# STM32f103c8t6.net
KiCad netlist of a schematic drawn in Altium Designer
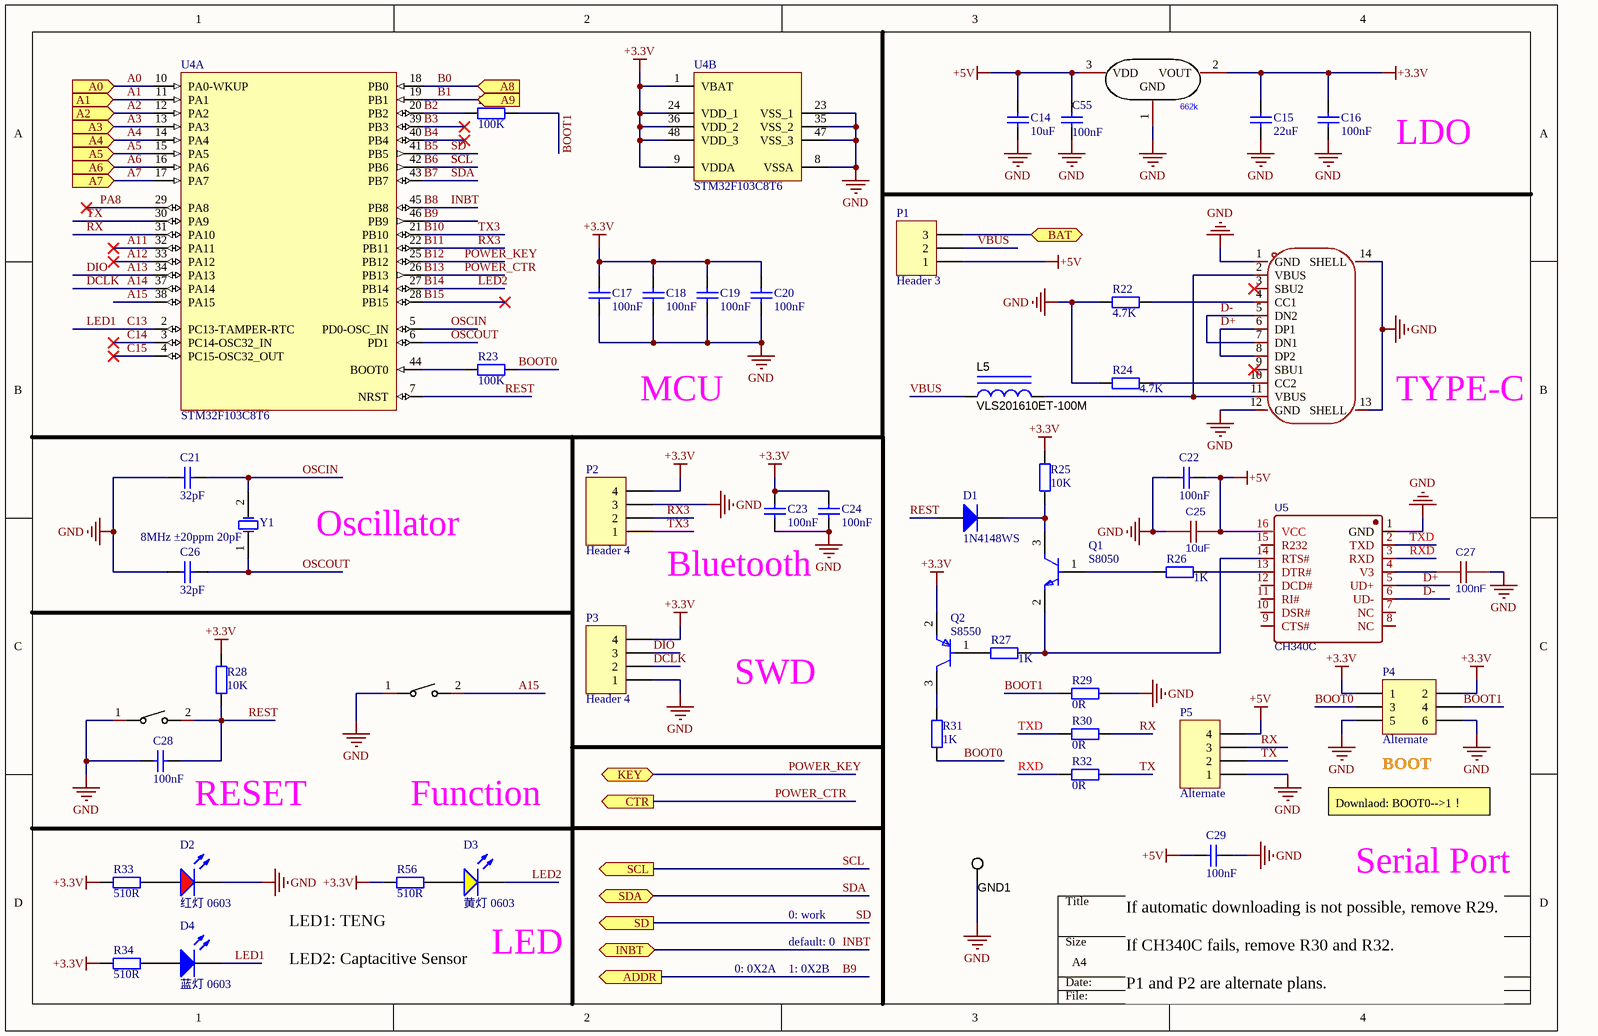
[diagram p0: STM32f103c8t6.SchDoc]

(export (version "E")
  (design (tool "Eeschema 10.0.6"))
  (components
    (comp (ref "C14")
      (value "10uF")
      (footprint "FDC2214:0603")
      (description "0402贴片电容")
      (libsource (lib "02-Miscellaneous_Devices_ZSF_Library") (part "Cap_0402"))
    )
    (comp (ref "C15")
      (value "22uF")
      (footprint "FDC2214:0603")
      (description "0402贴片电容")
      (libsource (lib "02-Miscellaneous_Devices_ZSF_Library") (part "Cap_0402"))
    )
    (comp (ref "C16")
      (value "100nF")
      (footprint "0402_C")
      (description "0402贴片电容")
      (libsource (lib "02-Miscellaneous_Devices_ZSF_Library") (part "Cap_0402"))
    )
    (comp (ref "C17")
      (value "100nF")
      (footprint "0402_C")
      (description "0402贴片电容")
      (libsource (lib "02-Miscellaneous_Devices_ZSF_Library") (part "Cap_0402"))
    )
    (comp (ref "C18")
      (value "100nF")
      (footprint "0402_C")
      (description "0402贴片电容")
      (libsource (lib "02-Miscellaneous_Devices_ZSF_Library") (part "Cap_0402"))
    )
    (comp (ref "C19")
      (value "100nF")
      (footprint "0402_C")
      (description "0402贴片电容")
      (libsource (lib "02-Miscellaneous_Devices_ZSF_Library") (part "Cap_0402"))
    )
    (comp (ref "C20")
      (value "100nF")
      (footprint "0402_C")
      (description "0402贴片电容")
      (libsource (lib "02-Miscellaneous_Devices_ZSF_Library") (part "Cap_0402"))
    )
    (comp (ref "C21")
      (value "32pF")
      (footprint "0402_C")
      (description "0402贴片电容")
      (libsource (lib "02-Miscellaneous_Devices_ZSF_Library") (part "Cap_0402"))
    )
    (comp (ref "C22")
      (value "100nF")
      (footprint "0402_C")
      (description "0402贴片电容")
      (libsource (lib "02-Miscellaneous_Devices_ZSF_Library") (part "Cap_0402"))
    )
    (comp (ref "C23")
      (value "100nF")
      (footprint "0402_C")
      (description "0402贴片电容")
      (libsource (lib "02-Miscellaneous_Devices_ZSF_Library") (part "Cap_0402"))
    )
    (comp (ref "C24")
      (value "100nF")
      (footprint "0402_C")
      (description "0402贴片电容")
      (libsource (lib "02-Miscellaneous_Devices_ZSF_Library") (part "Cap_0402"))
    )
    (comp (ref "C25")
      (value "10uF")
      (footprint "0402_C")
      (fields
        (field (name "BOM_MANUFACTURER PART") "XH414HG-IV01E")
        (field (name "BOM_SUPPLIER PART") "C38065")
      )
      (libsource (lib "XR_ADSCH_Library") (part "C"))
    )
    (comp (ref "C26")
      (value "32pF")
      (footprint "0402_C")
      (description "0402贴片电容")
      (libsource (lib "02-Miscellaneous_Devices_ZSF_Library") (part "Cap_0402"))
    )
    (comp (ref "C27")
      (value "100nF")
      (footprint "0402_C")
      (fields
        (field (name "BOM_MANUFACTURER PART") "XH414HG-IV01E")
        (field (name "BOM_SUPPLIER PART") "C38065")
      )
      (libsource (lib "XR_ADSCH_Library") (part "C"))
    )
    (comp (ref "C28")
      (value "100nF")
      (footprint "0402_C")
      (description "0402贴片电容")
      (libsource (lib "02-Miscellaneous_Devices_ZSF_Library") (part "Cap_0402"))
    )
    (comp (ref "C29")
      (value "100nF")
      (footprint "0402_C")
      (description "0402贴片电容")
      (libsource (lib "02-Miscellaneous_Devices_ZSF_Library") (part "Cap_0402"))
    )
    (comp (ref "C55")
      (value "100nF")
      (footprint "0402_C")
      (description "0402贴片电容")
      (libsource (lib "02-Miscellaneous_Devices_ZSF_Library") (part "Cap_0402"))
    )
    (comp (ref "D1")
      (value "1N4148WS")
      (footprint "SOD-323")
      (description "二极管")
      (libsource (lib "02-Miscellaneous_Devices_ZSF_Library") (part "1N4148WS_SOD-323"))
    )
    (comp (ref "D2")
      (value "红灯 0603")
      (footprint "0603_LED_S1")
      (description "发光二极管")
      (libsource (lib "02-Miscellaneous_Devices_ZSF_Library") (part "0603 红灯"))
    )
    (comp (ref "D3")
      (value "黄灯 0603")
      (footprint "0603_LED_S1")
      (description "发光二极管")
      (libsource (lib "02-Miscellaneous_Devices_ZSF_Library") (part "0603 黄灯"))
    )
    (comp (ref "D4")
      (value "蓝灯 0603")
      (footprint "0603_LED_S1")
      (description "发光二极管")
      (libsource (lib "02-Miscellaneous_Devices_ZSF_Library") (part "0603 蓝灯"))
    )
    (comp (ref "GND1")
      (value "5015")
      (footprint "Testpoint_Keystone_Miniature")
      (description "Test Point, Miniature, SMT")
      (fields (field (name "MANUFACTURER") "Keystone") (field (name "PUBLISHER") "Texas Instruments"))
      (libsource (lib "Connectors_Keystone") (part "5015"))
    )
    (comp (ref "L5")
      (value "VLS201610ET-100M")
      (footprint "VLS201610ET")
      (description "Inductor, Shielded, Ferrite, 10 μH, 0.4 A, 1.38 ohm, SMD")
      (fields (field (name "MANUFACTURER") "TDK") (field (name "PUBLISHER") "Texas Instruments"))
      (libsource (lib "Inductor_TDK") (part "VLS201610ET-100M"))
    )
    (comp (ref "LDO1")
      (value "662k")
      (footprint "SOT-23-3_L2.9-W1.3-P1.90-LS2.4-BR")
      (fields (field (name "MANUFACTURER") "FM(富满)") (field (name "MANUFACTURER PART") "SC662K-3.3V"))
      (libsource (lib "Chip") (part "SC662K-3.3V"))
    )
    (comp (ref "P1")
      (value "Header 3")
      (footprint "SIP-3")
      (description "Header, 3-Pin")
      (fields (field (name "PUBLISHER") "Altium Limited"))
      (libsource (lib "01-Connect_IntegratedLibrary") (part "Header 3"))
    )
    (comp (ref "P2")
      (value "Header 4")
      (footprint "XH254-4")
      (description "Header, 4-Pin")
      (fields (field (name "PUBLISHER") "Altium Limited"))
      (libsource (lib "01-Connect_IntegratedLibrary") (part "Header 4"))
    )
    (comp (ref "P3")
      (value "Header 4")
      (footprint "SIP-4")
      (description "Header, 4-Pin")
      (fields (field (name "PUBLISHER") "Altium Limited"))
      (libsource (lib "01-Connect_IntegratedLibrary") (part "Header 4"))
    )
    (comp (ref "P4")
      (value "Alternate")
      (footprint "01-Connect_IntegratedLibrary:HDR2X3 - SMT")
      (description "Header, 3-Pin, Dual row")
      (fields (field (name "PUBLISHER") "Altium Limited"))
      (libsource (lib "01-Connect_IntegratedLibrary") (part "Header 3X2"))
    )
    (comp (ref "P5")
      (value "Alternate")
      (footprint "SIP-4")
      (description "Header, 4-Pin")
      (fields (field (name "PUBLISHER") "Altium Limited"))
      (libsource (lib "01-Connect_IntegratedLibrary") (part "Header 4"))
    )
    (comp (ref "Q1")
      (value "S8050")
      (footprint "FP-SS8050-G-IPC_B")
      (description "NPN TRANSISTOR 1.5A 40V SOT-23 R")
      (libsource (lib "Chip") (part "S8050"))
    )
    (comp (ref "Q2")
      (value "S8550")
      (footprint "FP-SOT-23-IPC_A")
      (description "TRANS PNP 25V 1.5A SOT23")
      (libsource (lib "Chip") (part "S8550"))
    )
    (comp (ref "R21")
      (value "100K")
      (footprint "0402_R")
      (description "贴片电阻")
      (libsource (lib "02-Miscellaneous_Devices_ZSF_Library") (part "Res_0402"))
    )
    (comp (ref "R22")
      (value "4.7K")
      (footprint "0402_R")
      (description "贴片电阻")
      (libsource (lib "02-Miscellaneous_Devices_ZSF_Library") (part "Res_0402"))
    )
    (comp (ref "R23")
      (value "100K")
      (footprint "0402_R")
      (description "贴片电阻")
      (libsource (lib "02-Miscellaneous_Devices_ZSF_Library") (part "Res_0402"))
    )
    (comp (ref "R24")
      (value "4.7K")
      (footprint "0402_R")
      (description "贴片电阻")
      (libsource (lib "02-Miscellaneous_Devices_ZSF_Library") (part "Res_0402"))
    )
    (comp (ref "R25")
      (value "10K")
      (footprint "0402_R")
      (description "贴片电阻")
      (libsource (lib "") (part "Res_0402_1"))
    )
    (comp (ref "R26")
      (value "1K")
      (footprint "0402_R")
      (description "贴片电阻")
      (libsource (lib "02-Miscellaneous_Devices_ZSF_Library") (part "Res_0402"))
    )
    (comp (ref "R27")
      (value "1K")
      (footprint "0402_R")
      (description "贴片电阻")
      (libsource (lib "02-Miscellaneous_Devices_ZSF_Library") (part "Res_0402"))
    )
    (comp (ref "R28")
      (value "10K")
      (footprint "0402_R")
      (description "贴片电阻")
      (libsource (lib "") (part "Res_0402_1"))
    )
    (comp (ref "R29")
      (value "0R")
      (footprint "0805_R")
      (description "0805贴片电阻")
      (libsource (lib "02-Miscellaneous_Devices_ZSF_Library") (part "Res_0805"))
    )
    (comp (ref "R30")
      (value "0R")
      (footprint "0805_R")
      (description "0805贴片电阻")
      (libsource (lib "02-Miscellaneous_Devices_ZSF_Library") (part "Res_0805"))
    )
    (comp (ref "R31")
      (value "1K")
      (footprint "0402_R")
      (description "0805贴片电阻")
      (libsource (lib "") (part "Res_0805_1"))
    )
    (comp (ref "R32")
      (value "0R")
      (footprint "0805_R")
      (description "0805贴片电阻")
      (libsource (lib "02-Miscellaneous_Devices_ZSF_Library") (part "Res_0805"))
    )
    (comp (ref "R33")
      (value "510R")
      (footprint "0402_R")
      (description "贴片电阻")
      (libsource (lib "") (part "Res_0402_2"))
    )
    (comp (ref "R34")
      (value "510R")
      (footprint "0402_R")
      (description "贴片电阻")
      (libsource (lib "") (part "Res_0402_2"))
    )
    (comp (ref "R56")
      (value "510R")
      (footprint "0402_R")
      (description "贴片电阻")
      (libsource (lib "") (part "Res_0402_2"))
    )
    (comp (ref "SW1")
      (value "TS-1088-AR02016")
      (footprint "SW-SMD_L3.9-W3.0-P4.45")
      (fields (field (name "MANUFACTURER") "XUNPU(讯普)"))
      (libsource (lib "Chip") (part "Key"))
    )
    (comp (ref "SW2")
      (value "TS-1088-AR02016")
      (footprint "SW-SMD_L3.9-W3.0-P4.45")
      (fields (field (name "MANUFACTURER") "XUNPU(讯普)"))
      (libsource (lib "Chip") (part "Key"))
    )
    (comp (ref "U4")
      (value "STM32F103C8T6")
      (footprint "LQFP-48_7x7x05P")
      (description "ARM")
      (libsource (lib "02-Miscellaneous_Devices_ZSF_Library") (part "STM32F103C8T6"))
    )
    (comp (ref "U5")
      (value "CH340C")
      (footprint "SOP-16_150MIL")
      (fields (field (name "BOM_SUPPLIER PART") "C84681"))
      (libsource (lib "altium-import") (part "root_0_mirrored_CH340C_"))
    )
    (comp (ref "USB1")
      (value "TYPE-C 16PIN 2MD(073)")
      (footprint "USB-C-SMD_TYPE-C-6PIN-2MD-073")
      (fields (field (name "MANUFACTURER") "SHOU HAN(首韩)"))
      (libsource (lib "Chip") (part "TYPE-C 16PIN 2MD(073)"))
    )
    (comp (ref "Y1")
      (value "8MHz ±20ppm 20pF")
      (footprint "SMD-5032_2P")
      (description "贴片晶振")
      (libsource (lib "02-Miscellaneous_Devices_ZSF_Library") (part "SMD-5032_2P 8MHz 20ppm 20pF"))
    )
  )
  (nets
    (net (code "1") (name "+3.3V") (class "Default")
      (node (ref "C15") (pin "1") (pinfunction "1_1") (pintype "passive"))
      (node (ref "C16") (pin "1") (pinfunction "1_1") (pintype "passive"))
      (node (ref "C17") (pin "2") (pinfunction "2_2") (pintype "passive"))
      (node (ref "C18") (pin "2") (pinfunction "2_2") (pintype "passive"))
      (node (ref "C19") (pin "2") (pinfunction "2_2") (pintype "passive"))
      (node (ref "C20") (pin "2") (pinfunction "2_2") (pintype "passive"))
      (node (ref "C23") (pin "2") (pinfunction "2_2") (pintype "passive"))
      (node (ref "C24") (pin "2") (pinfunction "2_2") (pintype "passive"))
      (node (ref "LDO1") (pin "2") (pinfunction "VOUT_2") (pintype "passive"))
      (node (ref "P2") (pin "4") (pinfunction "4_4") (pintype "passive"))
      (node (ref "P3") (pin "4") (pinfunction "4_4") (pintype "passive"))
      (node (ref "P4") (pin "1") (pinfunction "1_1") (pintype "passive"))
      (node (ref "P4") (pin "2") (pinfunction "2_2") (pintype "passive"))
      (node (ref "Q2") (pin "2") (pinfunction "E_2") (pintype "passive"))
      (node (ref "R25") (pin "2") (pinfunction "2_2") (pintype "passive"))
      (node (ref "R28") (pin "2") (pinfunction "2_2") (pintype "passive"))
      (node (ref "R33") (pin "2") (pinfunction "2_2") (pintype "passive"))
      (node (ref "R34") (pin "2") (pinfunction "2_2") (pintype "passive"))
      (node (ref "R56") (pin "2") (pinfunction "2_2") (pintype "passive"))
      (node (ref "U4") (pin "1") (pinfunction "VBAT_1") (pintype "power_in"))
      (node (ref "U4") (pin "24") (pinfunction "VDD_1_24") (pintype "power_in"))
      (node (ref "U4") (pin "36") (pinfunction "VDD_2_36") (pintype "power_in"))
      (node (ref "U4") (pin "48") (pinfunction "VDD_3_48") (pintype "power_in"))
      (node (ref "U4") (pin "9") (pinfunction "VDDA_9") (pintype "power_in"))
    )
    (net (code "2") (name "+5V") (class "Default")
      (node (ref "C14") (pin "1") (pinfunction "1_1") (pintype "passive"))
      (node (ref "C22") (pin "2") (pinfunction "2_2") (pintype "passive"))
      (node (ref "C25") (pin "1") (pinfunction "1_1") (pintype "passive"))
      (node (ref "C29") (pin "2") (pinfunction "2_2") (pintype "passive"))
      (node (ref "C55") (pin "2") (pinfunction "2_2") (pintype "passive"))
      (node (ref "LDO1") (pin "3") (pinfunction "VDD_3") (pintype "passive"))
      (node (ref "P1") (pin "1") (pinfunction "1_1") (pintype "passive"))
      (node (ref "P5") (pin "4") (pinfunction "4_4") (pintype "passive"))
      (node (ref "U5") (pin "16") (pinfunction "VCC_16") (pintype "passive"))
    )
    (net (code "3") (name "/A0") (class "Default")
      (node (ref "U4") (pin "10") (pinfunction "PA0-WKUP_10") (pintype "bidirectional"))
    )
    (net (code "4") (name "/A1") (class "Default")
      (node (ref "U4") (pin "11") (pinfunction "PA1_11") (pintype "bidirectional"))
    )
    (net (code "5") (name "/A2") (class "Default")
      (node (ref "U4") (pin "12") (pinfunction "PA2_12") (pintype "bidirectional"))
    )
    (net (code "6") (name "/A3") (class "Default")
      (node (ref "U4") (pin "13") (pinfunction "PA3_13") (pintype "bidirectional"))
    )
    (net (code "7") (name "/A4") (class "Default")
      (node (ref "U4") (pin "14") (pinfunction "PA4_14") (pintype "bidirectional"))
    )
    (net (code "8") (name "/A5") (class "Default")
      (node (ref "U4") (pin "15") (pinfunction "PA5_15") (pintype "bidirectional"))
    )
    (net (code "9") (name "/A6") (class "Default")
      (node (ref "U4") (pin "16") (pinfunction "PA6_16") (pintype "bidirectional"))
    )
    (net (code "10") (name "/A7") (class "Default")
      (node (ref "U4") (pin "17") (pinfunction "PA7_17") (pintype "bidirectional"))
    )
    (net (code "11") (name "/A11") (class "Default")
      (node (ref "U4") (pin "32") (pinfunction "PA11_32") (pintype "bidirectional+no_connect"))
    )
    (net (code "12") (name "/A12") (class "Default")
      (node (ref "U4") (pin "33") (pinfunction "PA12_33") (pintype "bidirectional+no_connect"))
    )
    (net (code "13") (name "/A13") (class "Default")
      (node (ref "P3") (pin "3") (pinfunction "3_3") (pintype "passive"))
      (node (ref "U4") (pin "34") (pinfunction "PA13_34") (pintype "bidirectional"))
    )
    (net (code "14") (name "/A14") (class "Default")
      (node (ref "P3") (pin "2") (pinfunction "2_2") (pintype "passive"))
      (node (ref "U4") (pin "37") (pinfunction "PA14_37") (pintype "bidirectional"))
    )
    (net (code "15") (name "/A15") (class "Default")
      (node (ref "SW1") (pin "2") (pinfunction "2_2") (pintype "passive"))
      (node (ref "U4") (pin "38") (pinfunction "PA15_38") (pintype "bidirectional"))
    )
    (net (code "16") (name "/B0") (class "Default")
      (node (ref "U4") (pin "18") (pinfunction "PB0_18") (pintype "bidirectional"))
    )
    (net (code "17") (name "/B1") (class "Default")
      (node (ref "U4") (pin "19") (pinfunction "PB1_19") (pintype "bidirectional"))
    )
    (net (code "18") (name "/B2") (class "Default")
      (node (ref "R21") (pin "1") (pinfunction "1_1") (pintype "passive"))
      (node (ref "U4") (pin "20") (pinfunction "PB2_20") (pintype "bidirectional"))
    )
    (net (code "19") (name "/B3") (class "Default")
      (node (ref "U4") (pin "39") (pinfunction "PB3_39") (pintype "bidirectional+no_connect"))
    )
    (net (code "20") (name "/B4") (class "Default")
      (node (ref "U4") (pin "40") (pinfunction "PB4_40") (pintype "bidirectional+no_connect"))
    )
    (net (code "21") (name "/B5") (class "Default")
      (node (ref "U4") (pin "41") (pinfunction "PB5_41") (pintype "bidirectional"))
    )
    (net (code "22") (name "/B6") (class "Default")
      (node (ref "U4") (pin "42") (pinfunction "PB6_42") (pintype "bidirectional"))
    )
    (net (code "23") (name "/B7") (class "Default")
      (node (ref "U4") (pin "43") (pinfunction "PB7_43") (pintype "bidirectional"))
    )
    (net (code "24") (name "/B8") (class "Default")
      (node (ref "U4") (pin "45") (pinfunction "PB8_45") (pintype "bidirectional"))
    )
    (net (code "25") (name "/B9") (class "Default")
      (node (ref "U4") (pin "46") (pinfunction "PB9_46") (pintype "bidirectional"))
    )
    (net (code "26") (name "/B10") (class "Default")
      (node (ref "P2") (pin "1") (pinfunction "1_1") (pintype "passive"))
      (node (ref "U4") (pin "21") (pinfunction "PB10_21") (pintype "bidirectional"))
    )
    (net (code "27") (name "/B11") (class "Default")
      (node (ref "P2") (pin "2") (pinfunction "2_2") (pintype "passive"))
      (node (ref "U4") (pin "22") (pinfunction "PB11_22") (pintype "bidirectional"))
    )
    (net (code "28") (name "/B12") (class "Default")
      (node (ref "U4") (pin "25") (pinfunction "PB12_25") (pintype "bidirectional"))
    )
    (net (code "29") (name "/B13") (class "Default")
      (node (ref "U4") (pin "26") (pinfunction "PB13_26") (pintype "bidirectional"))
    )
    (net (code "30") (name "/B14") (class "Default")
      (node (ref "D3") (pin "K") (pinfunction "K_K") (pintype "passive"))
      (node (ref "U4") (pin "27") (pinfunction "PB14_27") (pintype "bidirectional"))
    )
    (net (code "31") (name "/B15") (class "Default")
      (node (ref "U4") (pin "28") (pinfunction "PB15_28") (pintype "bidirectional+no_connect"))
    )
    (net (code "32") (name "/BAT") (class "Default")
      (node (ref "P1") (pin "3") (pinfunction "3_3") (pintype "passive"))
    )
    (net (code "33") (name "/BOOT0") (class "Default")
      (node (ref "P4") (pin "3") (pinfunction "3_3") (pintype "passive"))
      (node (ref "R23") (pin "2") (pinfunction "2_2") (pintype "passive"))
      (node (ref "R31") (pin "1") (pinfunction "1_1") (pintype "passive"))
    )
    (net (code "34") (name "/BOOT1") (class "Default")
      (node (ref "P4") (pin "4") (pinfunction "4_4") (pintype "passive"))
      (node (ref "R21") (pin "2") (pinfunction "2_2") (pintype "passive"))
      (node (ref "R29") (pin "1") (pinfunction "1_1") (pintype "passive"))
    )
    (net (code "35") (name "/C13") (class "Default")
      (node (ref "D4") (pin "K") (pinfunction "K_K") (pintype "passive"))
      (node (ref "U4") (pin "2") (pinfunction "PC13-TAMPER-RTC_2") (pintype "bidirectional"))
    )
    (net (code "36") (name "/C14") (class "Default")
      (node (ref "U4") (pin "3") (pinfunction "PC14-OSC32_IN_3") (pintype "bidirectional+no_connect"))
    )
    (net (code "37") (name "/C15") (class "Default")
      (node (ref "U4") (pin "4") (pinfunction "PC15-OSC32_OUT_4") (pintype "bidirectional+no_connect"))
    )
    (net (code "38") (name "/D+") (class "Default")
      (node (ref "U5") (pin "5") (pinfunction "UD+_5") (pintype "passive"))
      (node (ref "USB1") (pin "6") (pinfunction "DP1_6") (pintype "passive"))
      (node (ref "USB1") (pin "8") (pinfunction "DP2_8") (pintype "passive"))
    )
    (net (code "39") (name "/D-") (class "Default")
      (node (ref "U5") (pin "6") (pinfunction "UD-_6") (pintype "passive"))
      (node (ref "USB1") (pin "5") (pinfunction "DN2_5") (pintype "passive"))
      (node (ref "USB1") (pin "7") (pinfunction "DN1_7") (pintype "passive"))
    )
    (net (code "40") (name "/OSCIN") (class "Default")
      (node (ref "C21") (pin "2") (pinfunction "2_2") (pintype "passive"))
      (node (ref "U4") (pin "5") (pinfunction "PD0-OSC_IN_5") (pintype "bidirectional"))
      (node (ref "Y1") (pin "2") (pinfunction "OSC2_2") (pintype "passive"))
    )
    (net (code "41") (name "/OSCOUT") (class "Default")
      (node (ref "C26") (pin "2") (pinfunction "2_2") (pintype "passive"))
      (node (ref "U4") (pin "6") (pinfunction "PD1_6") (pintype "bidirectional"))
      (node (ref "Y1") (pin "1") (pinfunction "OSC1_1") (pintype "passive"))
    )
    (net (code "42") (name "/PA8") (class "Default")
      (node (ref "U4") (pin "29") (pinfunction "PA8_29") (pintype "bidirectional+no_connect"))
    )
    (net (code "43") (name "/REST") (class "Default")
      (node (ref "C28") (pin "1") (pinfunction "1_1") (pintype "passive"))
      (node (ref "D1") (pin "1") (pinfunction "A_1") (pintype "passive"))
      (node (ref "R28") (pin "1") (pinfunction "1_1") (pintype "passive"))
      (node (ref "SW2") (pin "2") (pinfunction "2_2") (pintype "passive"))
      (node (ref "U4") (pin "7") (pinfunction "NRST_7") (pintype "bidirectional"))
    )
    (net (code "44") (name "/RX") (class "Default")
      (node (ref "P5") (pin "3") (pinfunction "3_3") (pintype "passive"))
      (node (ref "R30") (pin "2") (pinfunction "2_2") (pintype "passive"))
      (node (ref "U4") (pin "31") (pinfunction "PA10_31") (pintype "bidirectional"))
    )
    (net (code "45") (name "/RXD") (class "Default")
      (node (ref "R32") (pin "1") (pinfunction "1_1") (pintype "passive"))
      (node (ref "U5") (pin "3") (pinfunction "RXD_3") (pintype "passive"))
    )
    (net (code "46") (name "/TX") (class "Default")
      (node (ref "P5") (pin "2") (pinfunction "2_2") (pintype "passive"))
      (node (ref "R32") (pin "2") (pinfunction "2_2") (pintype "passive"))
      (node (ref "U4") (pin "30") (pinfunction "PA9_30") (pintype "bidirectional"))
    )
    (net (code "47") (name "/TXD") (class "Default")
      (node (ref "R30") (pin "1") (pinfunction "1_1") (pintype "passive"))
      (node (ref "U5") (pin "2") (pinfunction "TXD_2") (pintype "passive"))
    )
    (net (code "48") (name "/VBUS") (class "Default")
      (node (ref "L5") (pin "1") (pinfunction "1_1") (pintype "passive"))
      (node (ref "P1") (pin "2") (pinfunction "2_2") (pintype "passive"))
    )
    (net (code "49") (name "GND") (class "Default")
      (node (ref "C14") (pin "2") (pinfunction "2_2") (pintype "passive"))
      (node (ref "C15") (pin "2") (pinfunction "2_2") (pintype "passive"))
      (node (ref "C16") (pin "2") (pinfunction "2_2") (pintype "passive"))
      (node (ref "C17") (pin "1") (pinfunction "1_1") (pintype "passive"))
      (node (ref "C18") (pin "1") (pinfunction "1_1") (pintype "passive"))
      (node (ref "C19") (pin "1") (pinfunction "1_1") (pintype "passive"))
      (node (ref "C20") (pin "1") (pinfunction "1_1") (pintype "passive"))
      (node (ref "C21") (pin "1") (pinfunction "1_1") (pintype "passive"))
      (node (ref "C22") (pin "1") (pinfunction "1_1") (pintype "passive"))
      (node (ref "C23") (pin "1") (pinfunction "1_1") (pintype "passive"))
      (node (ref "C24") (pin "1") (pinfunction "1_1") (pintype "passive"))
      (node (ref "C25") (pin "2") (pinfunction "2_2") (pintype "passive"))
      (node (ref "C26") (pin "1") (pinfunction "1_1") (pintype "passive"))
      (node (ref "C27") (pin "2") (pinfunction "2_2") (pintype "passive"))
      (node (ref "C28") (pin "2") (pinfunction "2_2") (pintype "passive"))
      (node (ref "C29") (pin "1") (pinfunction "1_1") (pintype "passive"))
      (node (ref "C55") (pin "1") (pinfunction "1_1") (pintype "passive"))
      (node (ref "D2") (pin "K") (pinfunction "K_K") (pintype "passive"))
      (node (ref "GND1") (pin "1") (pintype "passive"))
      (node (ref "LDO1") (pin "1") (pinfunction "GND_1") (pintype "passive"))
      (node (ref "P2") (pin "3") (pinfunction "3_3") (pintype "passive"))
      (node (ref "P3") (pin "1") (pinfunction "1_1") (pintype "passive"))
      (node (ref "P4") (pin "5") (pinfunction "5_5") (pintype "passive"))
      (node (ref "P4") (pin "6") (pinfunction "6_6") (pintype "passive"))
      (node (ref "P5") (pin "1") (pinfunction "1_1") (pintype "passive"))
      (node (ref "R22") (pin "1") (pinfunction "1_1") (pintype "passive"))
      (node (ref "R24") (pin "1") (pinfunction "1_1") (pintype "passive"))
      (node (ref "R29") (pin "2") (pinfunction "2_2") (pintype "passive"))
      (node (ref "SW1") (pin "1") (pinfunction "1_1") (pintype "passive"))
      (node (ref "SW2") (pin "1") (pinfunction "1_1") (pintype "passive"))
      (node (ref "U4") (pin "23") (pinfunction "VSS_1_23") (pintype "power_in"))
      (node (ref "U4") (pin "35") (pinfunction "VSS_2_35") (pintype "power_in"))
      (node (ref "U4") (pin "47") (pinfunction "VSS_3_47") (pintype "power_in"))
      (node (ref "U4") (pin "8") (pinfunction "VSSA_8") (pintype "power_in"))
      (node (ref "U5") (pin "1") (pinfunction "GND_1") (pintype "passive"))
      (node (ref "USB1") (pin "1") (pinfunction "GND_1") (pintype "passive"))
      (node (ref "USB1") (pin "12") (pinfunction "GND_12") (pintype "passive"))
      (node (ref "USB1") (pin "13") (pinfunction "SHELL_13") (pintype "passive"))
      (node (ref "USB1") (pin "14") (pinfunction "SHELL_14") (pintype "passive"))
    )
    (net (code "50") (name "Net-(D1-K)") (class "Default")
      (node (ref "D1") (pin "2") (pinfunction "K_2") (pintype "passive"))
      (node (ref "Q1") (pin "3") (pinfunction "C_3") (pintype "passive"))
      (node (ref "R25") (pin "1") (pinfunction "1_1") (pintype "passive"))
    )
    (net (code "51") (name "Net-(D2-PadA)") (class "Default")
      (node (ref "D2") (pin "A") (pinfunction "A_A") (pintype "passive"))
      (node (ref "R33") (pin "1") (pinfunction "1_1") (pintype "passive"))
    )
    (net (code "52") (name "Net-(D3-PadA)") (class "Default")
      (node (ref "D3") (pin "A") (pinfunction "A_A") (pintype "passive"))
      (node (ref "R56") (pin "1") (pinfunction "1_1") (pintype "passive"))
    )
    (net (code "53") (name "Net-(D4-PadA)") (class "Default")
      (node (ref "D4") (pin "A") (pinfunction "A_A") (pintype "passive"))
      (node (ref "R34") (pin "1") (pinfunction "1_1") (pintype "passive"))
    )
    (net (code "54") (name "Net-(L5-Pad2)") (class "Default")
      (node (ref "L5") (pin "2") (pinfunction "2_2") (pintype "passive"))
      (node (ref "USB1") (pin "11") (pinfunction "VBUS_11") (pintype "passive"))
      (node (ref "USB1") (pin "2") (pinfunction "VBUS_2") (pintype "passive"))
    )
    (net (code "55") (name "Net-(Q1-B)") (class "Default")
      (node (ref "Q1") (pin "1") (pinfunction "B_1") (pintype "passive"))
      (node (ref "R26") (pin "1") (pinfunction "1_1") (pintype "passive"))
    )
    (net (code "56") (name "Net-(Q1-E)") (class "Default")
      (node (ref "Q1") (pin "2") (pinfunction "E_2") (pintype "passive"))
      (node (ref "R27") (pin "2") (pinfunction "2_2") (pintype "passive"))
      (node (ref "U5") (pin "14") (pinfunction "RTS#_14") (pintype "passive"))
    )
    (net (code "57") (name "Net-(Q2-B)") (class "Default")
      (node (ref "Q2") (pin "1") (pinfunction "B_1") (pintype "passive"))
      (node (ref "R27") (pin "1") (pinfunction "1_1") (pintype "passive"))
    )
    (net (code "58") (name "Net-(Q2-C)") (class "Default")
      (node (ref "Q2") (pin "3") (pinfunction "C_3") (pintype "passive"))
      (node (ref "R31") (pin "2") (pinfunction "2_2") (pintype "passive"))
    )
    (net (code "59") (name "Net-(U4A-BOOT0)") (class "Default")
      (node (ref "R23") (pin "1") (pinfunction "1_1") (pintype "passive"))
      (node (ref "U4") (pin "44") (pinfunction "BOOT0_44") (pintype "input"))
    )
    (net (code "60") (name "Net-(U5-DTR#)") (class "Default")
      (node (ref "R26") (pin "2") (pinfunction "2_2") (pintype "passive"))
      (node (ref "U5") (pin "13") (pinfunction "DTR#_13") (pintype "passive"))
    )
    (net (code "61") (name "Net-(U5-V3)") (class "Default")
      (node (ref "C27") (pin "1") (pinfunction "1_1") (pintype "passive"))
      (node (ref "U5") (pin "4") (pinfunction "V3_4") (pintype "passive"))
    )
    (net (code "62") (name "Net-(USB1-CC1)") (class "Default")
      (node (ref "R22") (pin "2") (pinfunction "2_2") (pintype "passive"))
      (node (ref "USB1") (pin "4") (pinfunction "CC1_4") (pintype "passive"))
    )
    (net (code "63") (name "Net-(USB1-CC2)") (class "Default")
      (node (ref "R24") (pin "2") (pinfunction "2_2") (pintype "passive"))
      (node (ref "USB1") (pin "10") (pinfunction "CC2_10") (pintype "passive"))
    )
    (net (code "64") (name "unconnected-(U5-CTS#-Pad9)") (class "Default")
      (node (ref "U5") (pin "9") (pinfunction "CTS#_9") (pintype "passive"))
    )
    (net (code "65") (name "unconnected-(U5-DCD#-Pad12)") (class "Default")
      (node (ref "U5") (pin "12") (pinfunction "DCD#_12") (pintype "passive"))
    )
    (net (code "66") (name "unconnected-(U5-DSR#-Pad10)") (class "Default")
      (node (ref "U5") (pin "10") (pinfunction "DSR#_10") (pintype "passive"))
    )
    (net (code "67") (name "unconnected-(U5-NC-Pad7)") (class "Default")
      (node (ref "U5") (pin "7") (pinfunction "NC_7") (pintype "passive"))
    )
    (net (code "68") (name "unconnected-(U5-NC-Pad8)") (class "Default")
      (node (ref "U5") (pin "8") (pinfunction "NC_8") (pintype "passive"))
    )
    (net (code "69") (name "unconnected-(U5-R232-Pad15)") (class "Default")
      (node (ref "U5") (pin "15") (pinfunction "R232_15") (pintype "passive"))
    )
    (net (code "70") (name "unconnected-(U5-RI#-Pad11)") (class "Default")
      (node (ref "U5") (pin "11") (pinfunction "RI#_11") (pintype "passive"))
    )
    (net (code "71") (name "unconnected-(USB1-SBU1-Pad9)") (class "Default")
      (node (ref "USB1") (pin "9") (pinfunction "SBU1_9") (pintype "passive+no_connect"))
    )
    (net (code "72") (name "unconnected-(USB1-SBU2-Pad3)") (class "Default")
      (node (ref "USB1") (pin "3") (pinfunction "SBU2_3") (pintype "passive+no_connect"))
    )
  )
)
